# Analog.net
KiCad netlist of a schematic drawn in Altium Designer
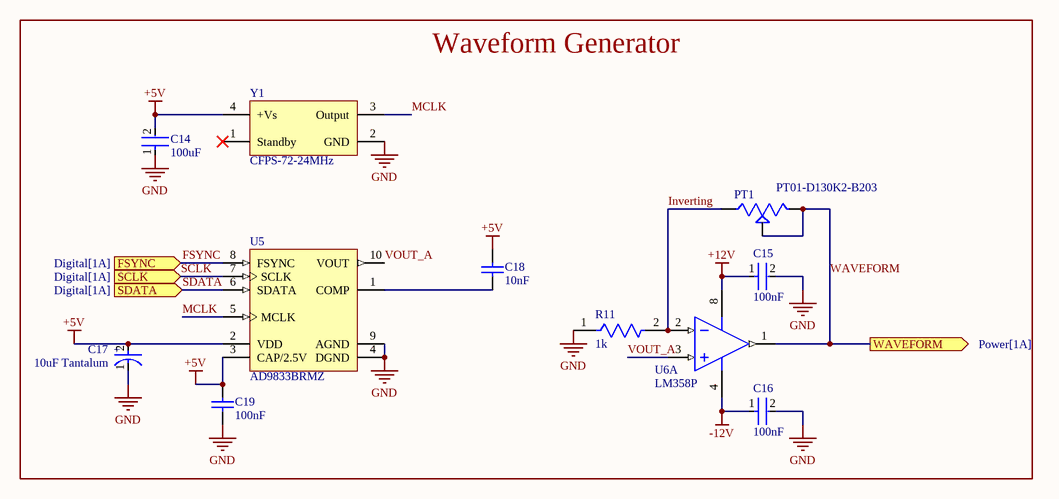
[diagram p0: Analog.SchDoc]

(export (version "E")
  (design (tool "Eeschema 10.0.6"))
  (components
    (comp (ref "C14")
      (value "100uF")
      (footprint "FP-C1206C-EB-MFG")
      (description "C1206 0.10 μF C0G 10.00% 25 V X7R")
      (fields
        (field (name "TOLERANCE") "0.1")
        (field (name "OCTOPART") "https://octopart.com/c1206c104k3gactu-kemet-12901041")
      )
      (libsource (lib "Altium Content Vault") (part "b4654b650e69147ec39a6b967a45e02"))
    )
    (comp (ref "C15")
      (value "100nF")
      (footprint "FP-C1206C-EB-MFG")
      (description "C1206 0.10 μF C0G 10.00% 25 V X7R")
      (fields
        (field (name "TOLERANCE") "0.1")
        (field (name "OCTOPART") "https://octopart.com/c1206c104k3gactu-kemet-12901041")
      )
      (libsource (lib "Altium Content Vault") (part "b4654b650e69147ec39a6b967a45e02"))
    )
    (comp (ref "C16")
      (value "100nF")
      (footprint "FP-C1206C-EB-MFG")
      (description "C1206 0.10 μF C0G 10.00% 25 V X7R")
      (fields
        (field (name "TOLERANCE") "0.1")
        (field (name "OCTOPART") "https://octopart.com/c1206c104k3gactu-kemet-12901041")
      )
      (libsource (lib "Altium Content Vault") (part "b4654b650e69147ec39a6b967a45e02"))
    )
    (comp (ref "C17")
      (value "10uF Tantalum")
      (footprint "FP-293DB-MFG")
      (description "CAP TANT 10UF 10% 20V 1411")
      (fields (field (name "VOLTAGE") "20V") (field (name "TOLERANCE") "10%"))
      (libsource (lib "Altium Content Vault") (part "a00bbbee19879c290e62620ae7e47b1"))
    )
    (comp (ref "C18")
      (value "10nF")
      (footprint "CAPC1206(3216)150_L")
      (description "CAP 10nF 10V ±5% 1206 (3216 Metric) Thickness 1.45mm SMD")
      (fields (field (name "TOLERANCE") "Â±5%"))
      (libsource (lib "Altium Content Vault") (part "CAP"))
    )
    (comp (ref "C19")
      (value "100nF")
      (footprint "CAPC1608X87X45LL20T05")
      (description "Ceramic 100nF X7R 16V 5% 1206")
      (fields (field (name "PART NUMBER") "C0603X104J4RACTU") (field (name "MANUFACTURER") "Kemet"))
      (libsource (lib "Altium Content Vault") (part "CAP"))
    )
    (comp (ref "PT1")
      (value "PT01-D130K2-B203")
      (footprint "TRIM_PT01-D130K2-B203")
      (libsource (lib "PT01-D130K2-B203") (part "PT01-D130K2-B203"))
    )
    (comp (ref "R11")
      (value "1k")
      (footprint "FP-MCU0805-IPC_B")
      (description "RES 1.05K OHM 0.5% 1/5W 0805")
      (libsource (lib "Altium Content Vault") (part "1029c3af85768c4190bb7ad29bc67b5"))
    )
    (comp (ref "U5")
      (value "AD9833BRMZ")
      (footprint "ADI-RM-10_M")
      (libsource (lib "Altium Content Vault") (part "ADI-AD9833-RM-10"))
    )
    (comp (ref "U6")
      (value "LM358P")
      (footprint "P0008A")
      (description "Dual Operational Amplifier, 3 to 32 V, 0 to 70 degC, 8-Pin PDIP (P), RoHS, Tape and Reel")
      (fields (field (name "MANUFACTURER") "Technik Industrial"))
      (libsource (lib "Altium Content Vault") (part "TI-LM_LPXXX-SO_DIP8"))
    )
    (comp (ref "Y1")
      (value "CFPS-72-24MHz")
      (footprint "WE-SPXO_CFPS-72")
      (description "831019082 WE-SPXO Crystal Oscillator")
      (libsource (lib "Altium Content Vault") (part "WE-SPXO_CFPS-72"))
    )
  )
  (nets
    (net (code "1") (name "+5V") (class "Default")
      (node (ref "C14") (pin "2") (pinfunction "2_2") (pintype "passive"))
      (node (ref "C17") (pin "2") (pinfunction "A_2") (pintype "passive"))
      (node (ref "C18") (pin "2") (pinfunction "2_2") (pintype "passive"))
      (node (ref "C19") (pin "2") (pinfunction "2_2") (pintype "passive"))
      (node (ref "U5") (pin "2") (pinfunction "VDD_2") (pintype "power_in"))
      (node (ref "U5") (pin "3") (pinfunction "CAP/2.5V_3") (pintype "power_in"))
      (node (ref "Y1") (pin "4") (pinfunction "+Vs_4") (pintype "passive"))
    )
    (net (code "2") (name "+12V") (class "Default")
      (node (ref "C15") (pin "1") (pinfunction "1_1") (pintype "passive"))
      (node (ref "U6") (pin "8") (pinfunction "VCC_8") (pintype "power_in"))
    )
    (net (code "3") (name "-12V") (class "Default")
      (node (ref "C16") (pin "1") (pinfunction "1_1") (pintype "passive"))
      (node (ref "U6") (pin "4") (pinfunction "GND_4") (pintype "power_in"))
    )
    (net (code "4") (name "/FSYNC") (class "Default")
      (node (ref "U5") (pin "8") (pinfunction "FSYNC_8") (pintype "input"))
    )
    (net (code "5") (name "/Inverting") (class "Default")
      (node (ref "PT1") (pin "3") (pinfunction "3_3") (pintype "passive"))
      (node (ref "R11") (pin "2") (pinfunction "2_2") (pintype "passive"))
      (node (ref "U6") (pin "2") (pinfunction "1IN-_2") (pintype "input"))
    )
    (net (code "6") (name "/MCLK") (class "Default")
      (node (ref "U5") (pin "5") (pinfunction "MCLK_5") (pintype "input"))
      (node (ref "Y1") (pin "3") (pinfunction "Output_3") (pintype "passive"))
    )
    (net (code "7") (name "/SCLK") (class "Default")
      (node (ref "U5") (pin "7") (pinfunction "SCLK_7") (pintype "input"))
    )
    (net (code "8") (name "/SDATA") (class "Default")
      (node (ref "U5") (pin "6") (pinfunction "SDATA_6") (pintype "input"))
    )
    (net (code "9") (name "/VOUT_A") (class "Default")
      (node (ref "U5") (pin "10") (pinfunction "VOUT_10") (pintype "output"))
      (node (ref "U6") (pin "3") (pinfunction "1IN+_3") (pintype "input"))
    )
    (net (code "10") (name "/WAVEFORM") (class "Default")
      (node (ref "PT1") (pin "1") (pinfunction "1_1") (pintype "passive"))
      (node (ref "PT1") (pin "2") (pinfunction "2_2") (pintype "passive"))
      (node (ref "U6") (pin "1") (pinfunction "1OUT_1") (pintype "output"))
    )
    (net (code "11") (name "GND") (class "Default")
      (node (ref "C14") (pin "1") (pinfunction "1_1") (pintype "passive"))
      (node (ref "C15") (pin "2") (pinfunction "2_2") (pintype "passive"))
      (node (ref "C16") (pin "2") (pinfunction "2_2") (pintype "passive"))
      (node (ref "C17") (pin "1") (pinfunction "C_1") (pintype "passive"))
      (node (ref "C19") (pin "1") (pinfunction "1_1") (pintype "passive"))
      (node (ref "R11") (pin "1") (pinfunction "1_1") (pintype "passive"))
      (node (ref "U5") (pin "4") (pinfunction "DGND_4") (pintype "power_in"))
      (node (ref "U5") (pin "9") (pinfunction "AGND_9") (pintype "power_in"))
      (node (ref "Y1") (pin "2") (pinfunction "GND_2") (pintype "passive"))
    )
    (net (code "12") (name "Net-(U5-COMP)") (class "Default")
      (node (ref "C18") (pin "1") (pinfunction "1_1") (pintype "passive"))
      (node (ref "U5") (pin "1") (pinfunction "COMP_1") (pintype "passive"))
    )
    (net (code "13") (name "unconnected-(Y1-Standby-Pad1)") (class "Default")
      (node (ref "Y1") (pin "1") (pinfunction "Standby_1") (pintype "passive+no_connect"))
    )
  )
)
